# stepper_control_board.net
KiCad netlist of a schematic drawn in EasyEDA
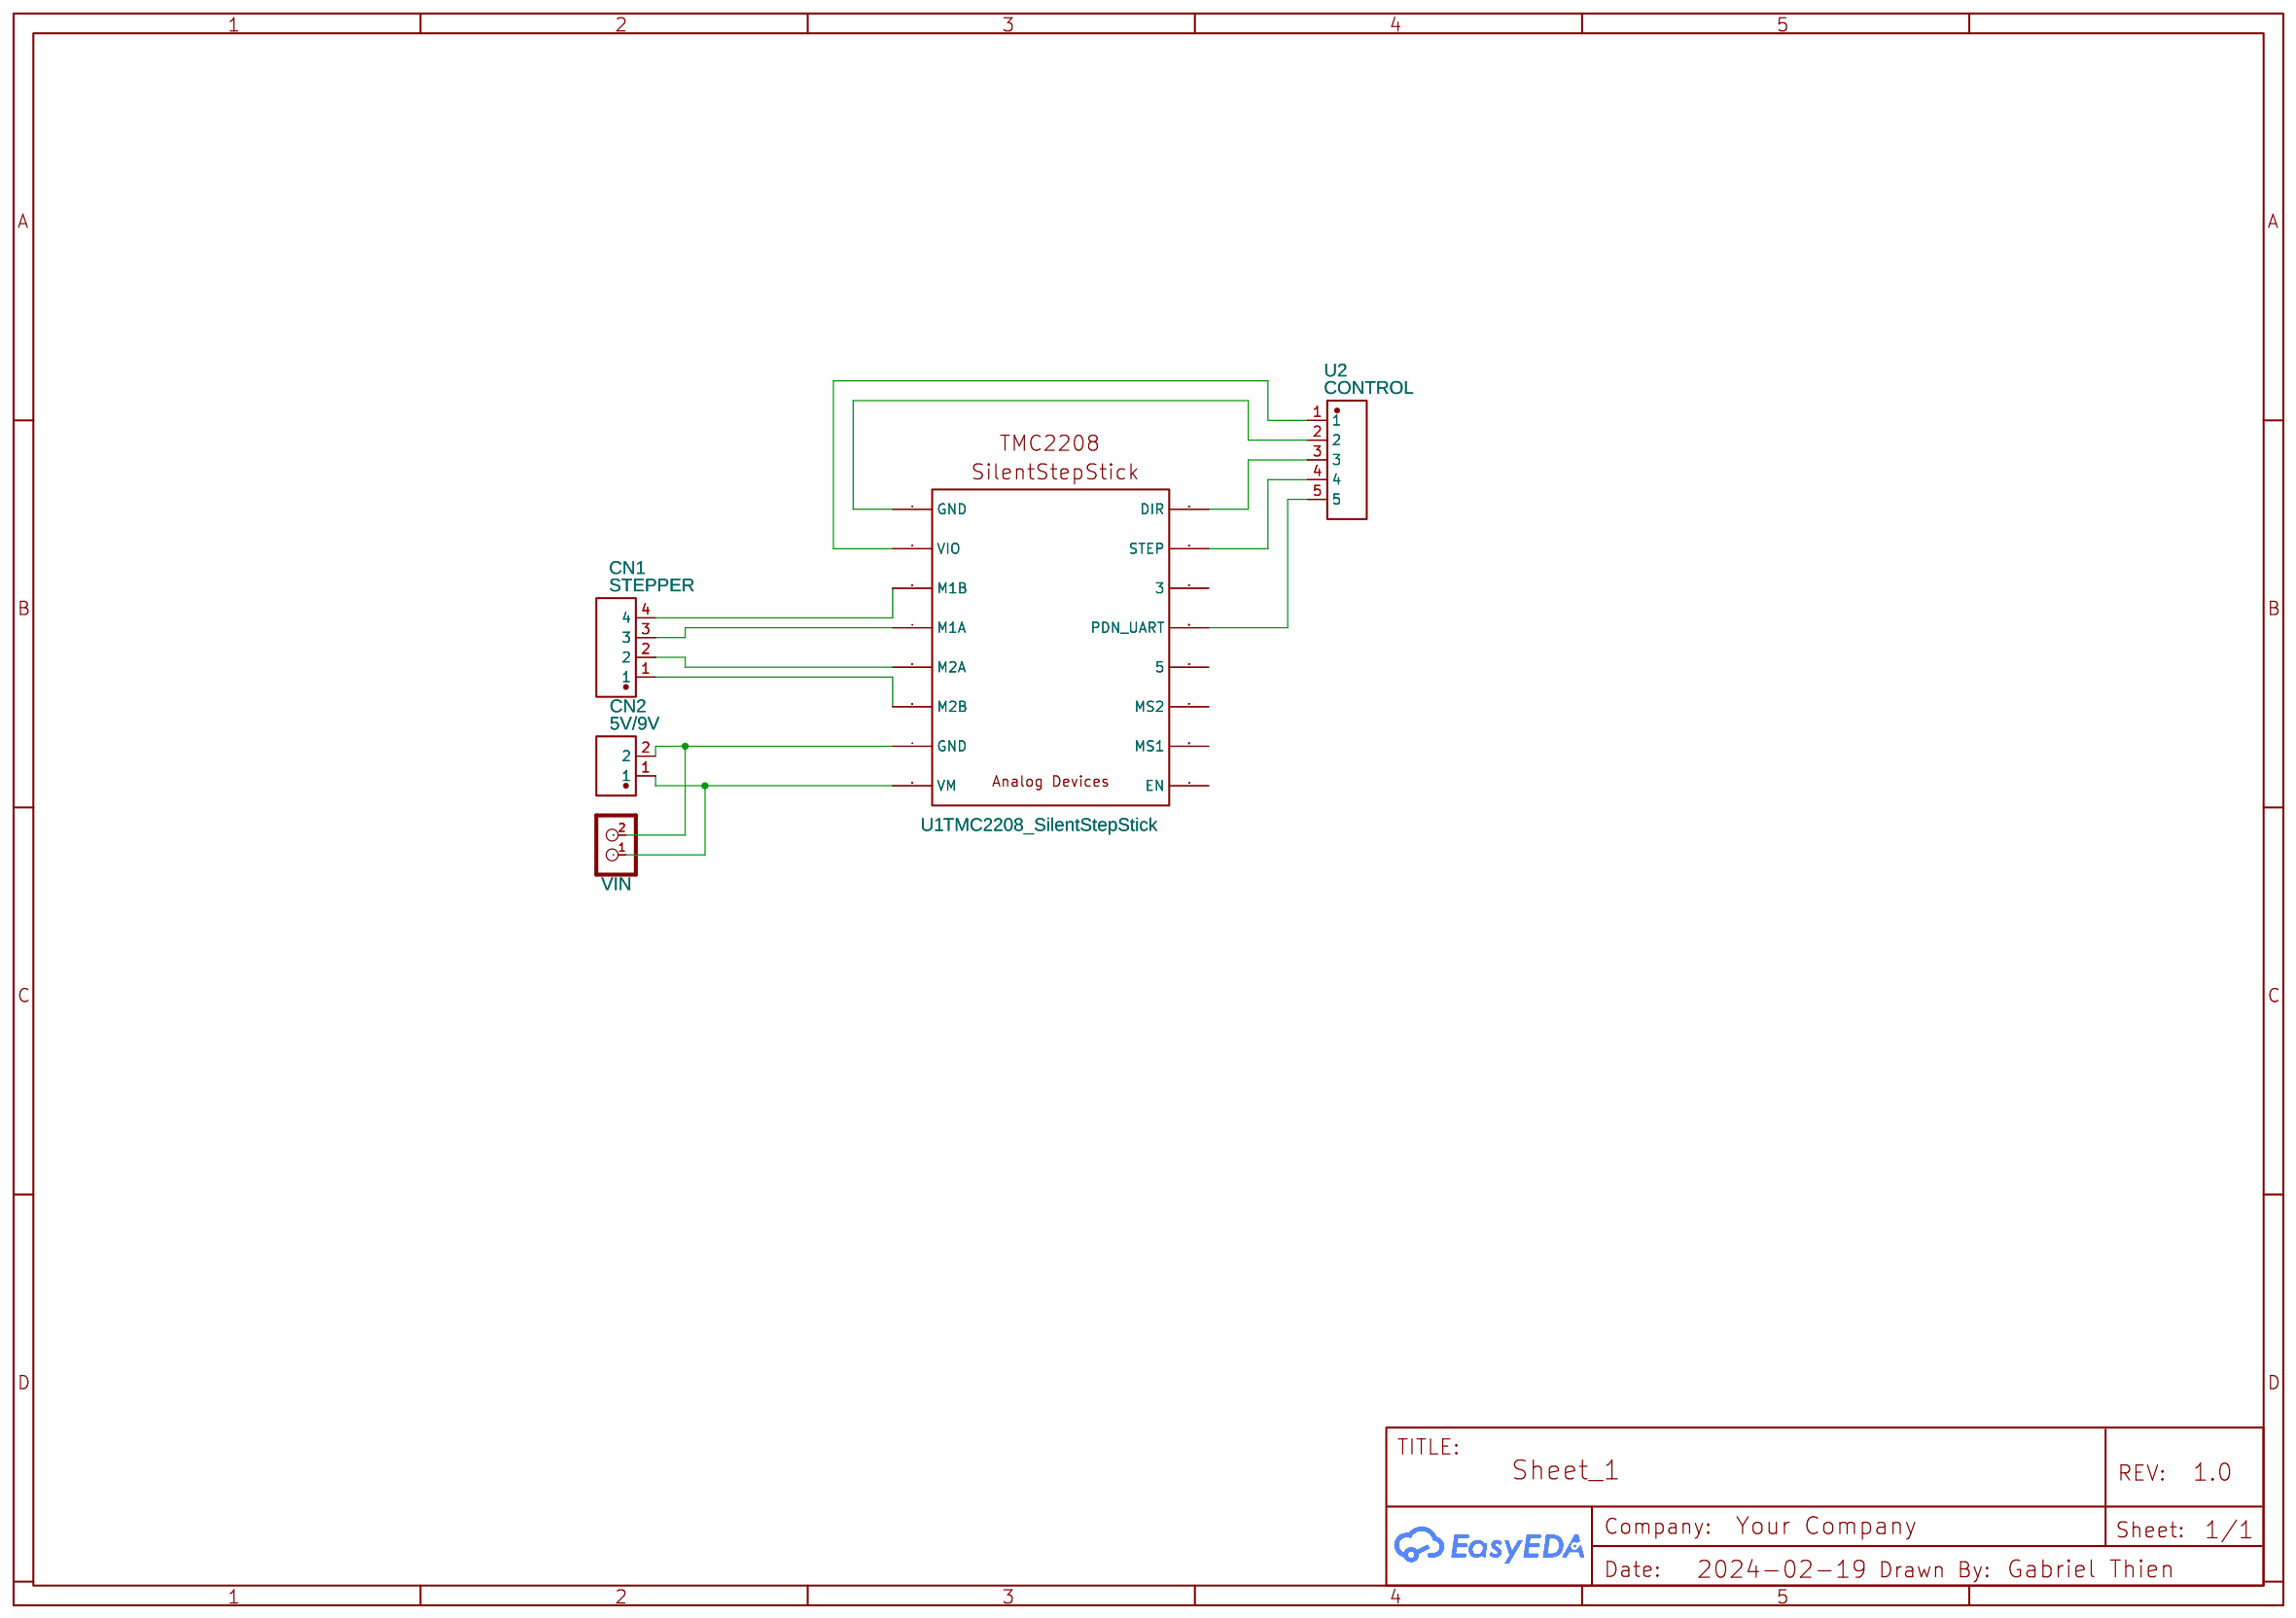
[diagram p0: schematic sheet]

(export (version "E")
  (design (tool "Eeschema 10.0.6"))
  (components
    (comp (ref "CN1")
      (value "STEPPER")
      (fields (field (name "Manufacturer Part") "XH4x2.54V"))
      (libsource (lib "") (part "XH4X2.54V"))
    )
    (comp (ref "CN2")
      (value "5V/9V")
      (fields (field (name "Manufacturer Part") "XH-D-2A") (field (name "Manufacturer") "DEALON(德艺隆)"))
      (libsource (lib "") (part "XH-D-2A"))
    )
    (comp (ref "U1") (value "TMC2208_SilentStepStick") (libsource (lib "") (part "TMC2208_SilentStepStick")))
    (comp (ref "U2")
      (value "CONTROL")
      (fields (field (name "Manufacturer Part") "XD-XH-5A-G") (field (name "Manufacturer") "XUNDA(讯答)"))
      (libsource (lib "") (part "XD-XH-5A-G"))
    )
    (comp (ref "VIN") (value "BT") (libsource (lib "") (part "CON_TERMINAL_BLOCK_02-5MM")))
  )
  (nets
    (net (code "1") (name "Net-(CN2-Pad2)") (class "Default")
      (node (ref "CN2") (pin "2") (pinfunction "2_2") (pintype "unspecified"))
      (node (ref "U1") (pin "7") (pinfunction "GND_7") (pintype "unspecified"))
      (node (ref "VIN") (pin "2") (pinfunction "2_2") (pintype "unspecified"))
    )
    (net (code "2") (name "Net-(U1-DIR)") (class "Default")
      (node (ref "U1") (pin "16") (pinfunction "DIR_16") (pintype "unspecified"))
      (node (ref "U2") (pin "3") (pinfunction "3_3") (pintype "unspecified"))
    )
    (net (code "3") (name "Net-(U1-GND-Pad1)") (class "Default")
      (node (ref "U1") (pin "1") (pinfunction "GND_1") (pintype "unspecified"))
      (node (ref "U2") (pin "2") (pinfunction "2_2") (pintype "unspecified"))
    )
    (net (code "4") (name "Net-(U1-M1A)") (class "Default")
      (node (ref "CN1") (pin "3") (pinfunction "3_3") (pintype "unspecified"))
      (node (ref "U1") (pin "4") (pinfunction "M1A_4") (pintype "unspecified"))
    )
    (net (code "5") (name "Net-(U1-M1B)") (class "Default")
      (node (ref "CN1") (pin "4") (pinfunction "4_4") (pintype "unspecified"))
      (node (ref "U1") (pin "3") (pinfunction "M1B_3") (pintype "unspecified"))
    )
    (net (code "6") (name "Net-(U1-M2A)") (class "Default")
      (node (ref "CN1") (pin "2") (pinfunction "2_2") (pintype "unspecified"))
      (node (ref "U1") (pin "5") (pinfunction "M2A_5") (pintype "unspecified"))
    )
    (net (code "7") (name "Net-(U1-M2B)") (class "Default")
      (node (ref "CN1") (pin "1") (pinfunction "1_1") (pintype "unspecified"))
      (node (ref "U1") (pin "6") (pinfunction "M2B_6") (pintype "unspecified"))
    )
    (net (code "8") (name "Net-(U1-PDN_UART)") (class "Default")
      (node (ref "U1") (pin "13") (pinfunction "PDN_UART_13") (pintype "unspecified"))
      (node (ref "U2") (pin "5") (pinfunction "5_5") (pintype "unspecified"))
    )
    (net (code "9") (name "Net-(U1-STEP)") (class "Default")
      (node (ref "U1") (pin "15") (pinfunction "STEP_15") (pintype "unspecified"))
      (node (ref "U2") (pin "4") (pinfunction "4_4") (pintype "unspecified"))
    )
    (net (code "10") (name "Net-(U1-VIO)") (class "Default")
      (node (ref "U1") (pin "2") (pinfunction "VIO_2") (pintype "unspecified"))
      (node (ref "U2") (pin "1") (pinfunction "1_1") (pintype "unspecified"))
    )
    (net (code "11") (name "Net-(U1-VM)") (class "Default")
      (node (ref "CN2") (pin "1") (pinfunction "1_1") (pintype "unspecified"))
      (node (ref "U1") (pin "8") (pinfunction "VM_8") (pintype "unspecified"))
      (node (ref "VIN") (pin "1") (pinfunction "1_1") (pintype "unspecified"))
    )
    (net (code "12") (name "unconnected-(U1-3-Pad14)") (class "Default")
      (node (ref "U1") (pin "14") (pinfunction "3_14") (pintype "unspecified"))
    )
    (net (code "13") (name "unconnected-(U1-5-Pad12)") (class "Default")
      (node (ref "U1") (pin "12") (pinfunction "5_12") (pintype "unspecified"))
    )
    (net (code "14") (name "unconnected-(U1-EN-Pad9)") (class "Default")
      (node (ref "U1") (pin "9") (pinfunction "EN_9") (pintype "unspecified"))
    )
    (net (code "15") (name "unconnected-(U1-MS1-Pad10)") (class "Default")
      (node (ref "U1") (pin "10") (pinfunction "MS1_10") (pintype "unspecified"))
    )
    (net (code "16") (name "unconnected-(U1-MS2-Pad11)") (class "Default")
      (node (ref "U1") (pin "11") (pinfunction "MS2_11") (pintype "unspecified"))
    )
  )
)
